# ICS-USB_Converter.net
KiCad netlist of a schematic drawn in EAGLE
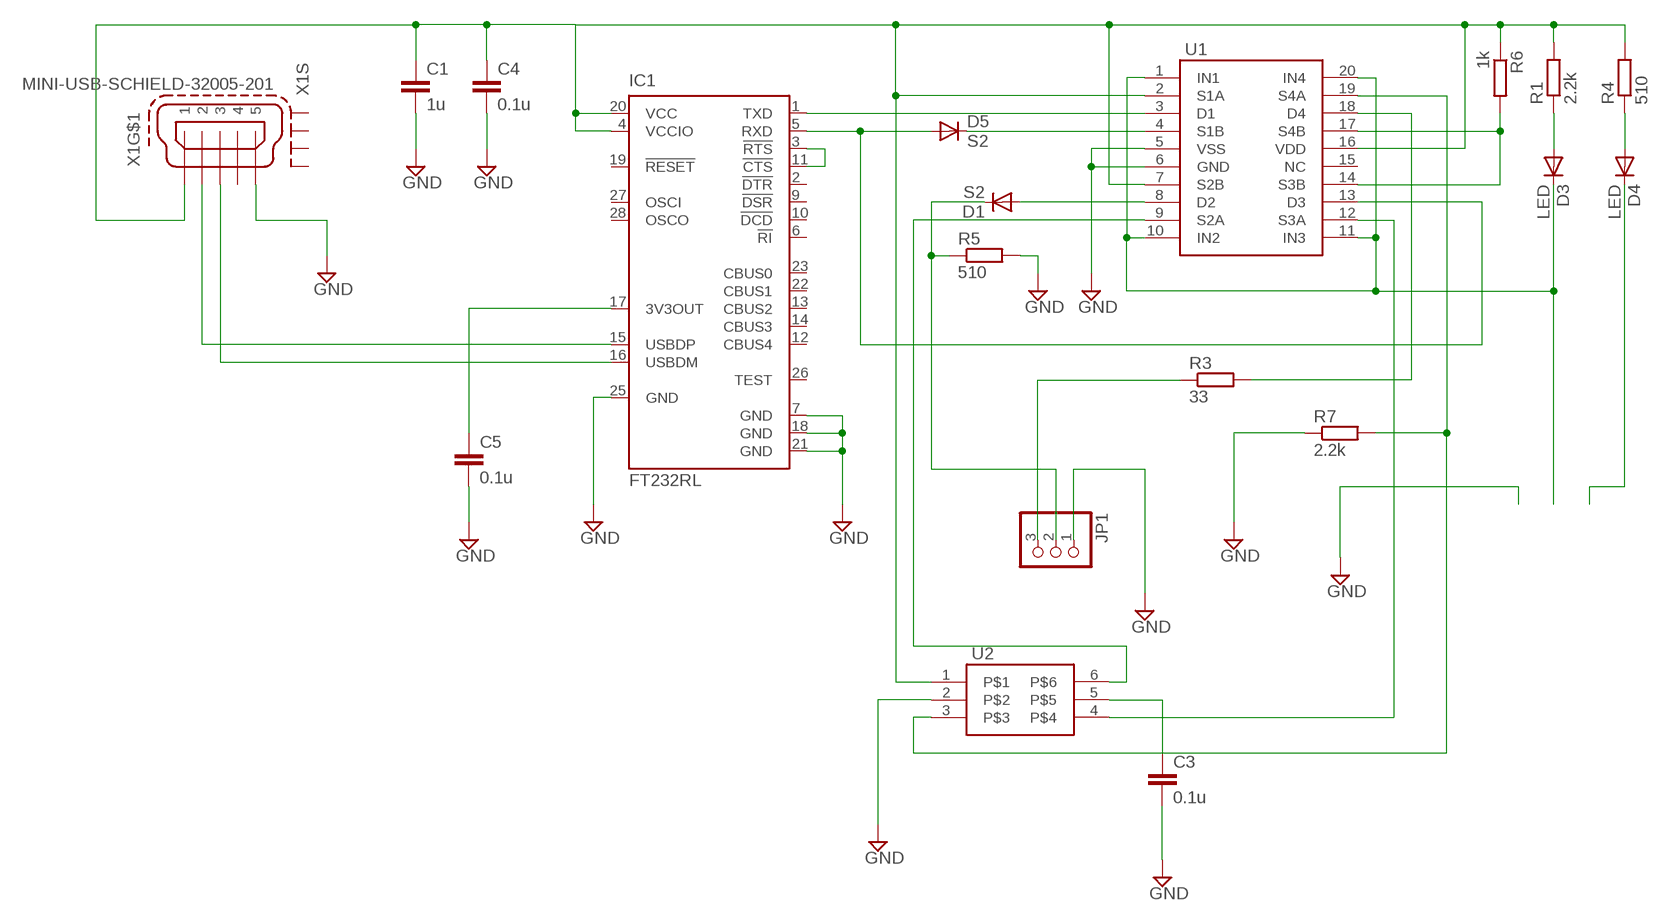
[diagram p0: schematic, sheet 1]

(export (version "E")
  (design (tool "Eeschema 10.0.6"))
  (components
    (comp (ref "C1")
      (value "1u")
      (footprint "eagle-import:C2012")
      (libsource (lib "eagle-import") (part "C-EUC2012"))
    )
    (comp (ref "C3")
      (value "0.1u")
      (footprint "eagle-import:C1608")
      (libsource (lib "eagle-import") (part "C-EUC1608"))
    )
    (comp (ref "C4")
      (value "0.1u")
      (footprint "eagle-import:C1608")
      (libsource (lib "eagle-import") (part "C-EUC1608"))
    )
    (comp (ref "C5")
      (value "0.1u")
      (footprint "eagle-import:C1608")
      (libsource (lib "eagle-import") (part "C-EUC1608"))
    )
    (comp (ref "D1")
      (value "S2")
      (footprint "eagle-import:SOD523")
      (libsource (lib "eagle-import") (part "DIODE-SOD523"))
    )
    (comp (ref "D3")
      (value "LED")
      (footprint "eagle-import:SOD523")
      (libsource (lib "eagle-import") (part "DIODE-SOD523"))
    )
    (comp (ref "D4")
      (value "LED")
      (footprint "eagle-import:SOD523")
      (libsource (lib "eagle-import") (part "DIODE-SOD523"))
    )
    (comp (ref "D5")
      (value "S2")
      (footprint "eagle-import:SOD523")
      (libsource (lib "eagle-import") (part "DIODE-SOD523"))
    )
    (comp (ref "IC1")
      (value "FT232RL")
      (footprint "eagle-import:SSOP28")
      (libsource (lib "eagle-import") (part "FT232RL"))
    )
    (comp (ref "JP1")
      (value "PINHD-1X3")
      (footprint "eagle-import:1X03")
      (libsource (lib "eagle-import") (part "PINHD-1X3"))
    )
    (comp (ref "R1")
      (value "2.2k")
      (footprint "eagle-import:C1608")
      (libsource (lib "eagle-import") (part "R-EU_R1608"))
    )
    (comp (ref "R3")
      (value "33")
      (footprint "eagle-import:C1608")
      (libsource (lib "eagle-import") (part "R-EU_R1608"))
    )
    (comp (ref "R4")
      (value "510")
      (footprint "eagle-import:C1608")
      (libsource (lib "eagle-import") (part "R-EU_R1608"))
    )
    (comp (ref "R5")
      (value "510")
      (footprint "eagle-import:C1608")
      (libsource (lib "eagle-import") (part "R-EU_R1608"))
    )
    (comp (ref "R6")
      (value "1k")
      (footprint "eagle-import:C1608")
      (libsource (lib "eagle-import") (part "R-EU_R1608"))
    )
    (comp (ref "R7")
      (value "2.2k")
      (footprint "eagle-import:C1608")
      (libsource (lib "eagle-import") (part "R-EU_R1608"))
    )
    (comp (ref "U1")
      (value "ADG734")
      (footprint "eagle-import:TSSOP20")
      (libsource (lib "eagle-import") (part "ADG734"))
    )
    (comp (ref "U2")
      (value "HA5SOT23-6")
      (footprint "eagle-import:SOT23-6")
      (libsource (lib "eagle-import") (part "HA5SOT23-6"))
    )
    (comp (ref "X1")
      (value "MINI-USB-SCHIELD-32005-201")
      (footprint "eagle-import:32005-201")
      (libsource (lib "eagle-import") (part "MINI-USB-SCHIELD-32005-201"))
    )
  )
  (nets
    (net (code "1") (name "GND") (class "Default")
      (node (ref "C1") (pin "2") (pinfunction "2_2") (pintype "passive"))
      (node (ref "C3") (pin "2") (pinfunction "2_2") (pintype "passive"))
      (node (ref "C4") (pin "2") (pinfunction "2_2") (pintype "passive"))
      (node (ref "C5") (pin "2") (pinfunction "2_2") (pintype "passive"))
      (node (ref "IC1") (pin "18") (pinfunction "GND_18") (pintype "power_in"))
      (node (ref "IC1") (pin "21") (pinfunction "GND_21") (pintype "power_in"))
      (node (ref "IC1") (pin "25") (pinfunction "GND_25") (pintype "power_in"))
      (node (ref "IC1") (pin "7") (pinfunction "GND_7") (pintype "power_in"))
      (node (ref "JP1") (pin "1") (pinfunction "1_1") (pintype "passive"))
      (node (ref "R5") (pin "2") (pinfunction "2_2") (pintype "passive"))
      (node (ref "R7") (pin "1") (pinfunction "1_1") (pintype "passive"))
      (node (ref "U1") (pin "5") (pinfunction "VSS_5") (pintype "bidirectional"))
      (node (ref "U1") (pin "6") (pinfunction "GND_6") (pintype "bidirectional"))
      (node (ref "U2") (pin "2") (pinfunction "P$2_2") (pintype "bidirectional"))
      (node (ref "X1") (pin "5") (pinfunction "5_5") (pintype "passive"))
    )
    (net (code "2") (name "Net-(D1-PadC)") (class "Default")
      (node (ref "D1") (pin "C") (pinfunction "C_C") (pintype "passive"))
      (node (ref "JP1") (pin "2") (pinfunction "2_2") (pintype "passive"))
      (node (ref "R5") (pin "1") (pinfunction "1_1") (pintype "passive"))
    )
    (net (code "3") (name "Net-(D3-PadA)") (class "Default")
      (node (ref "D3") (pin "A") (pinfunction "A_A") (pintype "passive"))
      (node (ref "R1") (pin "1") (pinfunction "1_1") (pintype "passive"))
    )
    (net (code "4") (name "Net-(D4-PadA)") (class "Default")
      (node (ref "D4") (pin "A") (pinfunction "A_A") (pintype "passive"))
      (node (ref "R4") (pin "1") (pinfunction "1_1") (pintype "passive"))
    )
    (net (code "5") (name "Net-(IC1-3V3OUT)") (class "Default")
      (node (ref "C5") (pin "1") (pinfunction "1_1") (pintype "passive"))
      (node (ref "IC1") (pin "17") (pinfunction "3V3OUT_17") (pintype "output"))
    )
    (net (code "6") (name "Net-(IC1-RXD)") (class "Default")
      (node (ref "D5") (pin "A") (pinfunction "A_A") (pintype "passive"))
      (node (ref "IC1") (pin "5") (pinfunction "RXD_5") (pintype "input"))
      (node (ref "U1") (pin "13") (pinfunction "D3_13") (pintype "bidirectional"))
    )
    (net (code "7") (name "Net-(IC1-TXD)") (class "Default")
      (node (ref "IC1") (pin "1") (pinfunction "TXD_1") (pintype "output"))
      (node (ref "U1") (pin "3") (pinfunction "D1_3") (pintype "bidirectional"))
    )
    (net (code "8") (name "Net-(IC1-USBDM)") (class "Default")
      (node (ref "IC1") (pin "16") (pinfunction "USBDM_16") (pintype "bidirectional"))
      (node (ref "X1") (pin "3") (pinfunction "3_3") (pintype "passive"))
    )
    (net (code "9") (name "Net-(IC1-USBDP)") (class "Default")
      (node (ref "IC1") (pin "15") (pinfunction "USBDP_15") (pintype "bidirectional"))
      (node (ref "X1") (pin "2") (pinfunction "2_2") (pintype "passive"))
    )
    (net (code "10") (name "Net-(IC1-VCC)") (class "Default")
      (node (ref "C1") (pin "1") (pinfunction "1_1") (pintype "passive"))
      (node (ref "C4") (pin "1") (pinfunction "1_1") (pintype "passive"))
      (node (ref "IC1") (pin "20") (pinfunction "VCC_20") (pintype "power_in"))
      (node (ref "IC1") (pin "4") (pinfunction "VCCIO_4") (pintype "power_in"))
      (node (ref "R1") (pin "2") (pinfunction "2_2") (pintype "passive"))
      (node (ref "R4") (pin "2") (pinfunction "2_2") (pintype "passive"))
      (node (ref "R6") (pin "1") (pinfunction "1_1") (pintype "passive"))
      (node (ref "U1") (pin "16") (pinfunction "VDD_16") (pintype "bidirectional"))
      (node (ref "U1") (pin "2") (pinfunction "S1A_2") (pintype "bidirectional"))
      (node (ref "U1") (pin "7") (pinfunction "S2B_7") (pintype "bidirectional"))
      (node (ref "U2") (pin "1") (pinfunction "P$1_1") (pintype "bidirectional"))
      (node (ref "X1") (pin "1") (pinfunction "1_1") (pintype "passive"))
    )
    (net (code "11") (name "Net-(IC1-~{CTS})") (class "Default")
      (node (ref "IC1") (pin "11") (pinfunction "~{CTS}_11") (pintype "input"))
      (node (ref "IC1") (pin "3") (pinfunction "~{RTS}_3") (pintype "output"))
    )
    (net (code "12") (name "Net-(JP1-Pad3)") (class "Default")
      (node (ref "JP1") (pin "3") (pinfunction "3_3") (pintype "passive"))
      (node (ref "R3") (pin "1") (pinfunction "1_1") (pintype "passive"))
    )
    (net (code "13") (name "Net-(U1-D2)") (class "Default")
      (node (ref "D1") (pin "A") (pinfunction "A_A") (pintype "passive"))
      (node (ref "U1") (pin "8") (pinfunction "D2_8") (pintype "bidirectional"))
    )
    (net (code "14") (name "Net-(U1-D4)") (class "Default")
      (node (ref "R3") (pin "2") (pinfunction "2_2") (pintype "passive"))
      (node (ref "U1") (pin "18") (pinfunction "D4_18") (pintype "bidirectional"))
    )
    (net (code "15") (name "Net-(U1-IN1)") (class "Default")
      (node (ref "D3") (pin "C") (pinfunction "C_C") (pintype "passive"))
      (node (ref "U1") (pin "1") (pinfunction "IN1_1") (pintype "bidirectional"))
      (node (ref "U1") (pin "10") (pinfunction "IN2_10") (pintype "bidirectional"))
      (node (ref "U1") (pin "11") (pinfunction "IN3_11") (pintype "bidirectional"))
      (node (ref "U1") (pin "20") (pinfunction "IN4_20") (pintype "bidirectional"))
    )
    (net (code "16") (name "Net-(U1-S1B)") (class "Default")
      (node (ref "D5") (pin "C") (pinfunction "C_C") (pintype "passive"))
      (node (ref "U1") (pin "4") (pinfunction "S1B_4") (pintype "bidirectional"))
    )
    (net (code "17") (name "Net-(U1-S2A)") (class "Default")
      (node (ref "U1") (pin "9") (pinfunction "S2A_9") (pintype "bidirectional"))
      (node (ref "U2") (pin "6") (pinfunction "P$6_6") (pintype "bidirectional"))
    )
    (net (code "18") (name "Net-(U1-S3A)") (class "Default")
      (node (ref "U1") (pin "12") (pinfunction "S3A_12") (pintype "bidirectional"))
      (node (ref "U2") (pin "4") (pinfunction "P$4_4") (pintype "bidirectional"))
    )
    (net (code "19") (name "Net-(U1-S3B)") (class "Default")
      (node (ref "R6") (pin "2") (pinfunction "2_2") (pintype "passive"))
      (node (ref "U1") (pin "14") (pinfunction "S3B_14") (pintype "bidirectional"))
      (node (ref "U1") (pin "17") (pinfunction "S4B_17") (pintype "bidirectional"))
    )
    (net (code "20") (name "Net-(U1-S4A)") (class "Default")
      (node (ref "R7") (pin "2") (pinfunction "2_2") (pintype "passive"))
      (node (ref "U1") (pin "19") (pinfunction "S4A_19") (pintype "bidirectional"))
      (node (ref "U2") (pin "3") (pinfunction "P$3_3") (pintype "bidirectional"))
    )
    (net (code "21") (name "Net-(U2-P$5)") (class "Default")
      (node (ref "C3") (pin "1") (pinfunction "1_1") (pintype "passive"))
      (node (ref "U2") (pin "5") (pinfunction "P$5_5") (pintype "bidirectional"))
    )
    (net (code "22") (name "unconnected-(D4-PadC)") (class "Default")
      (node (ref "D4") (pin "C") (pinfunction "C_C") (pintype "passive"))
    )
    (net (code "23") (name "unconnected-(IC1-CBUS0-Pad23)") (class "Default")
      (node (ref "IC1") (pin "23") (pinfunction "CBUS0_23") (pintype "bidirectional"))
    )
    (net (code "24") (name "unconnected-(IC1-CBUS1-Pad22)") (class "Default")
      (node (ref "IC1") (pin "22") (pinfunction "CBUS1_22") (pintype "bidirectional"))
    )
    (net (code "25") (name "unconnected-(IC1-CBUS2-Pad13)") (class "Default")
      (node (ref "IC1") (pin "13") (pinfunction "CBUS2_13") (pintype "bidirectional"))
    )
    (net (code "26") (name "unconnected-(IC1-CBUS3-Pad14)") (class "Default")
      (node (ref "IC1") (pin "14") (pinfunction "CBUS3_14") (pintype "bidirectional"))
    )
    (net (code "27") (name "unconnected-(IC1-CBUS4-Pad12)") (class "Default")
      (node (ref "IC1") (pin "12") (pinfunction "CBUS4_12") (pintype "bidirectional"))
    )
    (net (code "28") (name "unconnected-(IC1-OSCI-Pad27)") (class "Default")
      (node (ref "IC1") (pin "27") (pinfunction "OSCI_27") (pintype "input"))
    )
    (net (code "29") (name "unconnected-(IC1-OSCO-Pad28)") (class "Default")
      (node (ref "IC1") (pin "28") (pinfunction "OSCO_28") (pintype "output"))
    )
    (net (code "30") (name "unconnected-(IC1-TEST-Pad26)") (class "Default")
      (node (ref "IC1") (pin "26") (pinfunction "TEST_26") (pintype "input"))
    )
    (net (code "31") (name "unconnected-(IC1-~{DCD}-Pad10)") (class "Default")
      (node (ref "IC1") (pin "10") (pinfunction "~{DCD}_10") (pintype "input"))
    )
    (net (code "32") (name "unconnected-(IC1-~{DSR}-Pad9)") (class "Default")
      (node (ref "IC1") (pin "9") (pinfunction "~{DSR}_9") (pintype "input"))
    )
    (net (code "33") (name "unconnected-(IC1-~{DTR}-Pad2)") (class "Default")
      (node (ref "IC1") (pin "2") (pinfunction "~{DTR}_2") (pintype "output"))
    )
    (net (code "34") (name "unconnected-(IC1-~{RESET}-Pad19)") (class "Default")
      (node (ref "IC1") (pin "19") (pinfunction "~{RESET}_19") (pintype "input"))
    )
    (net (code "35") (name "unconnected-(IC1-~{RI}-Pad6)") (class "Default")
      (node (ref "IC1") (pin "6") (pinfunction "~{RI}_6") (pintype "input"))
    )
    (net (code "36") (name "unconnected-(U1-NC-Pad15)") (class "Default")
      (node (ref "U1") (pin "15") (pinfunction "NC_15") (pintype "bidirectional"))
    )
    (net (code "37") (name "unconnected-(X1-Pad4)") (class "Default")
      (node (ref "X1") (pin "4") (pinfunction "4_4") (pintype "passive"))
    )
    (net (code "38") (name "unconnected-(X1B-S1-PadM1)") (class "Default")
      (node (ref "X1") (pin "M1") (pinfunction "S1_M1") (pintype "passive"))
    )
    (net (code "39") (name "unconnected-(X1B-S2-PadM2)") (class "Default")
      (node (ref "X1") (pin "M2") (pinfunction "S2_M2") (pintype "passive"))
    )
    (net (code "40") (name "unconnected-(X1B-S3-PadM3)") (class "Default")
      (node (ref "X1") (pin "M3") (pinfunction "S3_M3") (pintype "passive"))
    )
    (net (code "41") (name "unconnected-(X1B-S4-PadM4)") (class "Default")
      (node (ref "X1") (pin "M4") (pinfunction "S4_M4") (pintype "passive"))
    )
  )
)
